# mb_01-2.net
KiCad netlist of a schematic drawn in EAGLE
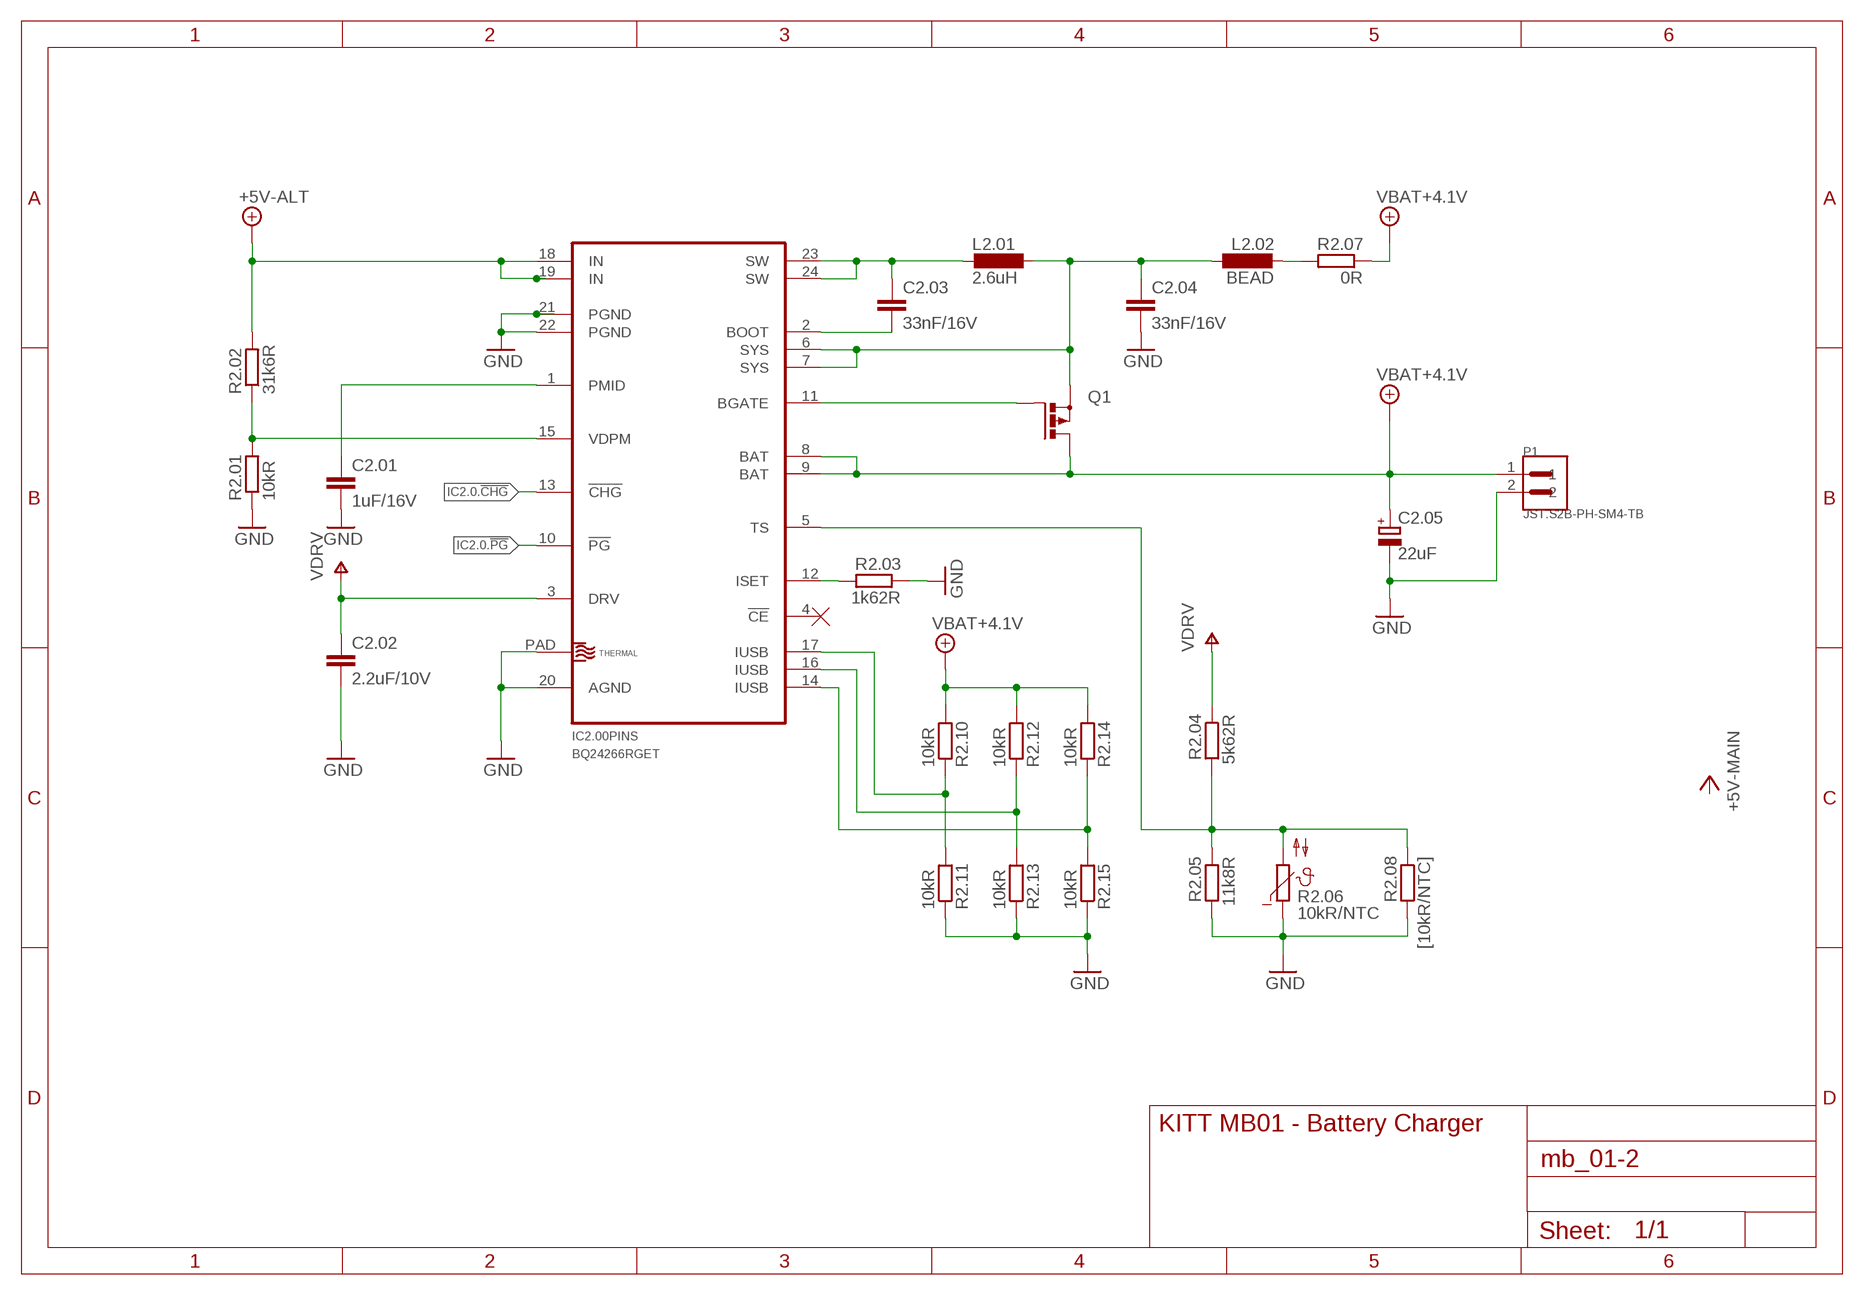
[diagram p0: schematic, sheet 1]

(export (version "E")
  (design (tool "Eeschema 10.0.6"))
  (components
    (comp (ref "C2.01")
      (value "1uF/16V")
      (footprint "eagle-import:C0805")
      (libsource (lib "eagle-import") (part "C-EUC0805"))
    )
    (comp (ref "C2.02")
      (value "2.2uF/10V")
      (footprint "eagle-import:C0603K")
      (libsource (lib "eagle-import") (part "C-EUC0603K"))
    )
    (comp (ref "C2.03")
      (value "33nF/16V")
      (footprint "eagle-import:C0603")
      (libsource (lib "eagle-import") (part "C-EUC0603"))
    )
    (comp (ref "C2.04")
      (value "33nF/16V")
      (footprint "eagle-import:C0805")
      (libsource (lib "eagle-import") (part "C-EUC0805"))
    )
    (comp (ref "C2.05")
      (value "22uF")
      (footprint "eagle-import:A_3216-18R")
      (libsource (lib "eagle-import") (part "CPOL-EUA/3216-18R"))
    )
    (comp (ref "IC2.00")
      (value "BQ24266RGET")
      (footprint "eagle-import:VQFN-24")
      (libsource (lib "eagle-import") (part "BQ24266RGET"))
    )
    (comp (ref "L2.01")
      (value "2.6uH")
      (footprint "eagle-import:POWER-CHOKE_WE-TPC")
      (libsource (lib "eagle-import") (part "L-EUWE-TPC"))
    )
    (comp (ref "L2.02")
      (value "BEAD")
      (footprint "eagle-import:L2012C")
      (libsource (lib "eagle-import") (part "L-EUL2012C"))
    )
    (comp (ref "P1")
      (value "JST.S2B-PH-SM4-TB")
      (footprint "eagle-import:JST_S2B-PH-SM4-TB(LF)(SN)")
      (fields (field (name "MF") "JST") (field (name "MP") "S2B-PH-SM4-TB(LF)(SN)"))
      (libsource (lib "eagle-import") (part "JST.S2B-PH-SM4-TB"))
    )
    (comp (ref "Q1")
      (value "P-MOSFET-SO8")
      (footprint "eagle-import:SO-08")
      (libsource (lib "eagle-import") (part "P-MOSFET-SO8"))
    )
    (comp (ref "R2.01")
      (value "10kR")
      (footprint "eagle-import:R0402")
      (libsource (lib "eagle-import") (part "R-EU_R0402"))
    )
    (comp (ref "R2.02")
      (value "31k6R")
      (footprint "eagle-import:R0402")
      (libsource (lib "eagle-import") (part "R-EU_R0402"))
    )
    (comp (ref "R2.03")
      (value "1k62R")
      (footprint "eagle-import:R0402")
      (libsource (lib "eagle-import") (part "R-EU_R0402"))
    )
    (comp (ref "R2.04")
      (value "5k62R")
      (footprint "eagle-import:R0402")
      (libsource (lib "eagle-import") (part "R-EU_R0402"))
    )
    (comp (ref "R2.05")
      (value "11k8R")
      (footprint "eagle-import:R0402")
      (libsource (lib "eagle-import") (part "R-EU_R0402"))
    )
    (comp (ref "R2.06")
      (value "10kR/NTC")
      (footprint "eagle-import:P642")
      (libsource (lib "eagle-import") (part "V642"))
    )
    (comp (ref "R2.07")
      (value "0R")
      (footprint "eagle-import:R0402")
      (libsource (lib "eagle-import") (part "R-EU_R0402"))
    )
    (comp (ref "R2.08")
      (value "[10kR/NTC]")
      (footprint "eagle-import:R0402")
      (libsource (lib "eagle-import") (part "R-EU_R0402"))
    )
    (comp (ref "R2.10")
      (value "10kR")
      (footprint "eagle-import:R0402")
      (libsource (lib "eagle-import") (part "R-EU_R0402"))
    )
    (comp (ref "R2.11")
      (value "10kR")
      (footprint "eagle-import:R0402")
      (libsource (lib "eagle-import") (part "R-EU_R0402"))
    )
    (comp (ref "R2.12")
      (value "10kR")
      (footprint "eagle-import:R0402")
      (libsource (lib "eagle-import") (part "R-EU_R0402"))
    )
    (comp (ref "R2.13")
      (value "10kR")
      (footprint "eagle-import:R0402")
      (libsource (lib "eagle-import") (part "R-EU_R0402"))
    )
    (comp (ref "R2.14")
      (value "10kR")
      (footprint "eagle-import:R0402")
      (libsource (lib "eagle-import") (part "R-EU_R0402"))
    )
    (comp (ref "R2.15")
      (value "10kR")
      (footprint "eagle-import:R0402")
      (libsource (lib "eagle-import") (part "R-EU_R0402"))
    )
  )
  (nets
    (net (code "1") (name "+5V-ALT") (class "Default")
      (node (ref "IC2.00") (pin "18") (pinfunction "IN_18") (pintype "bidirectional"))
      (node (ref "IC2.00") (pin "19") (pinfunction "IN_19") (pintype "bidirectional"))
      (node (ref "R2.02") (pin "2") (pinfunction "2_2") (pintype "passive"))
    )
    (net (code "3") (name "/IC2.0.~{CHG}") (class "Default")
      (node (ref "IC2.00") (pin "13") (pinfunction "~{CHG}_13") (pintype "bidirectional"))
    )
    (net (code "4") (name "/IC2.0.~{PG}") (class "Default")
      (node (ref "IC2.00") (pin "10") (pinfunction "~{PG}_10") (pintype "bidirectional"))
    )
    (net (code "5") (name "GND") (class "Default")
      (node (ref "C2.01") (pin "2") (pinfunction "2_2") (pintype "passive"))
      (node (ref "C2.02") (pin "2") (pinfunction "2_2") (pintype "passive"))
      (node (ref "C2.04") (pin "2") (pinfunction "2_2") (pintype "passive"))
      (node (ref "C2.05") (pin "-") (pinfunction "-_-") (pintype "passive"))
      (node (ref "IC2.00") (pin "20") (pinfunction "AGND_20") (pintype "bidirectional"))
      (node (ref "IC2.00") (pin "21") (pinfunction "PGND_21") (pintype "bidirectional"))
      (node (ref "IC2.00") (pin "22") (pinfunction "PGND_22") (pintype "bidirectional"))
      (node (ref "IC2.00") (pin "PAD") (pinfunction "THERMAL_PAD") (pintype "bidirectional"))
      (node (ref "P1") (pin "2") (pinfunction "2_2") (pintype "passive"))
      (node (ref "R2.01") (pin "1") (pinfunction "1_1") (pintype "passive"))
      (node (ref "R2.03") (pin "1") (pinfunction "1_1") (pintype "passive"))
      (node (ref "R2.05") (pin "2") (pinfunction "2_2") (pintype "passive"))
      (node (ref "R2.06") (pin "1") (pinfunction "1_1") (pintype "passive"))
      (node (ref "R2.08") (pin "2") (pinfunction "2_2") (pintype "passive"))
      (node (ref "R2.11") (pin "1") (pinfunction "1_1") (pintype "passive"))
      (node (ref "R2.13") (pin "1") (pinfunction "1_1") (pintype "passive"))
      (node (ref "R2.15") (pin "1") (pinfunction "1_1") (pintype "passive"))
    )
    (net (code "6") (name "Net-(C2.03-Pad1)") (class "Default")
      (node (ref "C2.03") (pin "1") (pinfunction "1_1") (pintype "passive"))
      (node (ref "IC2.00") (pin "23") (pinfunction "SW_23") (pintype "bidirectional"))
      (node (ref "IC2.00") (pin "24") (pinfunction "SW_24") (pintype "bidirectional"))
      (node (ref "L2.01") (pin "2") (pinfunction "2_2") (pintype "passive"))
    )
    (net (code "7") (name "Net-(C2.04-Pad1)") (class "Default")
      (node (ref "C2.04") (pin "1") (pinfunction "1_1") (pintype "passive"))
      (node (ref "IC2.00") (pin "6") (pinfunction "SYS_6") (pintype "bidirectional"))
      (node (ref "IC2.00") (pin "7") (pinfunction "SYS_7") (pintype "bidirectional"))
      (node (ref "L2.01") (pin "1") (pinfunction "1_1") (pintype "passive"))
      (node (ref "L2.02") (pin "1") (pinfunction "1_1") (pintype "passive"))
      (node (ref "Q1") (pin "1") (pinfunction "S_1") (pintype "passive"))
      (node (ref "Q1") (pin "2") (pinfunction "S_2") (pintype "passive"))
      (node (ref "Q1") (pin "3") (pinfunction "S_3") (pintype "passive"))
    )
    (net (code "8") (name "Net-(IC2.00B-BGATE)") (class "Default")
      (node (ref "IC2.00") (pin "11") (pinfunction "BGATE_11") (pintype "bidirectional"))
      (node (ref "Q1") (pin "4") (pinfunction "G_4") (pintype "passive"))
    )
    (net (code "9") (name "Net-(IC2.00B-BOOT)") (class "Default")
      (node (ref "C2.03") (pin "2") (pinfunction "2_2") (pintype "passive"))
      (node (ref "IC2.00") (pin "2") (pinfunction "BOOT_2") (pintype "bidirectional"))
    )
    (net (code "10") (name "Net-(IC2.00B-ISET)") (class "Default")
      (node (ref "IC2.00") (pin "12") (pinfunction "ISET_12") (pintype "bidirectional"))
      (node (ref "R2.03") (pin "2") (pinfunction "2_2") (pintype "passive"))
    )
    (net (code "11") (name "Net-(IC2.00B-IUSB-Pad14)") (class "Default")
      (node (ref "IC2.00") (pin "14") (pinfunction "IUSB_14") (pintype "bidirectional"))
      (node (ref "R2.14") (pin "1") (pinfunction "1_1") (pintype "passive"))
      (node (ref "R2.15") (pin "2") (pinfunction "2_2") (pintype "passive"))
    )
    (net (code "12") (name "Net-(IC2.00B-IUSB-Pad16)") (class "Default")
      (node (ref "IC2.00") (pin "16") (pinfunction "IUSB_16") (pintype "bidirectional"))
      (node (ref "R2.12") (pin "1") (pinfunction "1_1") (pintype "passive"))
      (node (ref "R2.13") (pin "2") (pinfunction "2_2") (pintype "passive"))
    )
    (net (code "13") (name "Net-(IC2.00B-IUSB-Pad17)") (class "Default")
      (node (ref "IC2.00") (pin "17") (pinfunction "IUSB_17") (pintype "bidirectional"))
      (node (ref "R2.10") (pin "1") (pinfunction "1_1") (pintype "passive"))
      (node (ref "R2.11") (pin "2") (pinfunction "2_2") (pintype "passive"))
    )
    (net (code "14") (name "Net-(IC2.00B-PMID)") (class "Default")
      (node (ref "C2.01") (pin "1") (pinfunction "1_1") (pintype "passive"))
      (node (ref "IC2.00") (pin "1") (pinfunction "PMID_1") (pintype "bidirectional"))
    )
    (net (code "15") (name "Net-(IC2.00B-TS)") (class "Default")
      (node (ref "IC2.00") (pin "5") (pinfunction "TS_5") (pintype "bidirectional"))
      (node (ref "R2.04") (pin "2") (pinfunction "2_2") (pintype "passive"))
      (node (ref "R2.05") (pin "1") (pinfunction "1_1") (pintype "passive"))
      (node (ref "R2.06") (pin "2") (pinfunction "2_2") (pintype "passive"))
      (node (ref "R2.08") (pin "1") (pinfunction "1_1") (pintype "passive"))
    )
    (net (code "16") (name "Net-(IC2.00B-VDPM)") (class "Default")
      (node (ref "IC2.00") (pin "15") (pinfunction "VDPM_15") (pintype "bidirectional"))
      (node (ref "R2.01") (pin "2") (pinfunction "2_2") (pintype "passive"))
      (node (ref "R2.02") (pin "1") (pinfunction "1_1") (pintype "passive"))
    )
    (net (code "17") (name "Net-(L2.02-Pad2)") (class "Default")
      (node (ref "L2.02") (pin "2") (pinfunction "2_2") (pintype "passive"))
      (node (ref "R2.07") (pin "2") (pinfunction "2_2") (pintype "passive"))
    )
    (net (code "18") (name "VBAT+4.1V") (class "Default")
      (node (ref "C2.05") (pin "+") (pinfunction "+_+") (pintype "passive"))
      (node (ref "IC2.00") (pin "8") (pinfunction "BAT_8") (pintype "bidirectional"))
      (node (ref "IC2.00") (pin "9") (pinfunction "BAT_9") (pintype "bidirectional"))
      (node (ref "P1") (pin "1") (pinfunction "1_1") (pintype "passive"))
      (node (ref "Q1") (pin "5") (pinfunction "D_5") (pintype "passive"))
      (node (ref "Q1") (pin "6") (pinfunction "D_6") (pintype "passive"))
      (node (ref "Q1") (pin "7") (pinfunction "D_7") (pintype "passive"))
      (node (ref "Q1") (pin "8") (pinfunction "D_8") (pintype "passive"))
      (node (ref "R2.07") (pin "1") (pinfunction "1_1") (pintype "passive"))
      (node (ref "R2.10") (pin "2") (pinfunction "2_2") (pintype "passive"))
      (node (ref "R2.12") (pin "2") (pinfunction "2_2") (pintype "passive"))
      (node (ref "R2.14") (pin "2") (pinfunction "2_2") (pintype "passive"))
    )
    (net (code "19") (name "VDRV") (class "Default")
      (node (ref "C2.02") (pin "1") (pinfunction "1_1") (pintype "passive"))
      (node (ref "IC2.00") (pin "3") (pinfunction "DRV_3") (pintype "bidirectional"))
      (node (ref "R2.04") (pin "1") (pinfunction "1_1") (pintype "passive"))
    )
    (net (code "20") (name "unconnected-(IC2.00B-~{CE}-Pad4)") (class "Default")
      (node (ref "IC2.00") (pin "4") (pinfunction "~{CE}_4") (pintype "bidirectional"))
    )
  )
)
